# 3_-MCU.net
KiCad netlist of a schematic drawn in Altium Designer
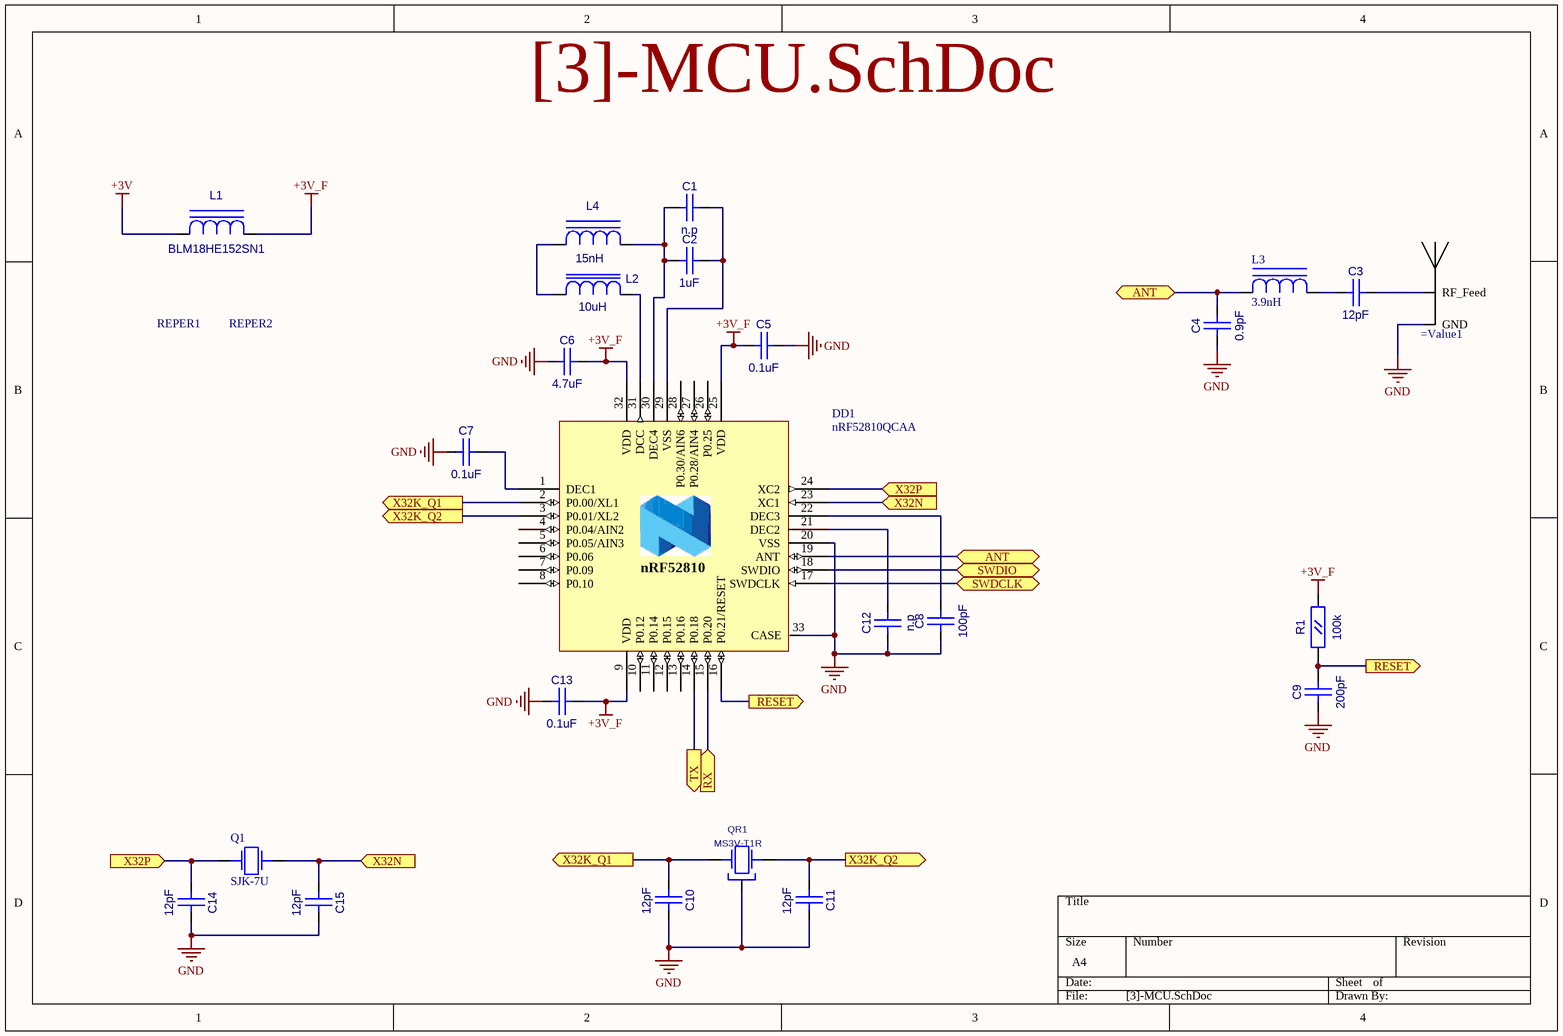
[diagram p0: [3]-MCU.SchDoc]

(export (version "E")
  (design (tool "Eeschema 10.0.6"))
  (components
    (comp (ref "=Value1")
      (value "ANTENNA_IFA_245_1MM")
      (footprint "IFA245_1mm")
      (description "Antenna 2.45GHz")
      (libsource (lib "fizik_lib") (part "ANTENNA_IFA_245_1MM"))
    )
    (comp (ref "C1")
      (value "n.p")
      (footprint "CC0805")
      (description "CC0805")
      (libsource (lib "fizik_lib") (part "CC0805"))
    )
    (comp (ref "C2")
      (value "1uF")
      (footprint "CC0603")
      (description "CC0603")
      (libsource (lib "gprs_modem_2") (part "CC0603"))
    )
    (comp (ref "C3")
      (value "12pF")
      (footprint "CC0603")
      (description "CC0603")
      (libsource (lib "") (part "CC0603_1"))
    )
    (comp (ref "C4")
      (value "0.9pF")
      (footprint "CC0603")
      (description "CC0603")
      (libsource (lib "fizik_lib") (part "CC0603"))
    )
    (comp (ref "C5")
      (value "0.1uF")
      (footprint "CC0603")
      (description "CC0603")
      (libsource (lib "gprs_modem_2") (part "CC0603"))
    )
    (comp (ref "C6")
      (value "4.7uF")
      (footprint "CC0805")
      (description "CC0805")
      (libsource (lib "fizik_lib") (part "CC0805"))
    )
    (comp (ref "C7")
      (value "0.1uF")
      (footprint "CC0603")
      (description "CC0603")
      (libsource (lib "gprs_modem_2") (part "CC0603"))
    )
    (comp (ref "C8")
      (value "100pF")
      (footprint "CC0603")
      (description "CC0603")
      (libsource (lib "gprs_modem_2") (part "CC0603"))
    )
    (comp (ref "C9")
      (value "200pF")
      (footprint "CC0603")
      (description "CC0603")
      (libsource (lib "gprs_modem_2") (part "CC0603"))
    )
    (comp (ref "C10")
      (value "12pF")
      (footprint "CC0603")
      (description "CC0603")
      (libsource (lib "gprs_modem_2") (part "CC0603"))
    )
    (comp (ref "C11")
      (value "12pF")
      (footprint "CC0603")
      (description "CC0603")
      (libsource (lib "gprs_modem_2") (part "CC0603"))
    )
    (comp (ref "C12")
      (value "n.p")
      (footprint "CC0603")
      (description "CC0603")
      (libsource (lib "gprs_modem_2") (part "CC0603"))
    )
    (comp (ref "C13")
      (value "0.1uF")
      (footprint "CC0603")
      (description "CC0603")
      (libsource (lib "gprs_modem_2") (part "CC0603"))
    )
    (comp (ref "C14")
      (value "12pF")
      (footprint "CC0603")
      (description "CC0603")
      (libsource (lib "gprs_modem_2") (part "CC0603"))
    )
    (comp (ref "C15")
      (value "12pF")
      (footprint "CC0603")
      (description "CC0603")
      (libsource (lib "gprs_modem_2") (part "CC0603"))
    )
    (comp (ref "DD1")
      (value "nRF52810QCAA")
      (footprint "QFN-32")
      (description "BLE 5 controller")
      (libsource (lib "fizik_lib") (part "NRF52810QCAA"))
    )
    (comp (ref "L1")
      (value "BLM18HE152SN1")
      (footprint "L0603")
      (description "L0603")
      (libsource (lib "gprs_modem_2") (part "L0603"))
    )
    (comp (ref "L2")
      (value "10uH")
      (footprint "RC0805")
      (description "L0805")
      (libsource (lib "gprs_modem_2") (part "L0805"))
    )
    (comp (ref "L3")
      (value "3.9nH")
      (footprint "L0402")
      (description "L0402")
      (libsource (lib "gprs_modem_2") (part "L0402"))
    )
    (comp (ref "L4")
      (value "15nH")
      (footprint "L0603")
      (description "L0603")
      (libsource (lib "fizik_lib") (part "L0603"))
    )
    (comp (ref "Q1")
      (value "SJK-7U")
      (footprint "QUARTZ_3225_4")
      (description "3.2x2.5mm 4 pin SMD quartz crystal")
      (libsource (lib "fizik_lib") (part "SJK-7U"))
    )
    (comp (ref "QR1")
      (value "MS3V-T1R")
      (footprint "MS3V-T1R")
      (description "CRYSTAL_32768 Hz")
      (libsource (lib "gprs_modem_2") (part "MS3V-T1R"))
    )
    (comp (ref "R1")
      (value "100k")
      (footprint "RC0603")
      (description "RC0603")
      (libsource (lib "gprs_modem_2") (part "RC0603"))
    )
    (comp (ref "REPER1")
      (value "REPER1.2")
      (footprint "REPER1.2")
      (libsource (lib "gprs_modem_2") (part "REPER1.2"))
    )
    (comp (ref "REPER2")
      (value "REPER1.2")
      (footprint "REPER1.2")
      (libsource (lib "gprs_modem_2") (part "REPER1.2"))
    )
  )
  (nets
    (net (code "1") (name "+3V") (class "Default")
      (node (ref "L1") (pin "1") (pinfunction "A_1") (pintype "passive"))
    )
    (net (code "2") (name "+3V_F") (class "Default")
      (node (ref "C13") (pin "2") (pinfunction "B_2") (pintype "passive"))
      (node (ref "C5") (pin "1") (pinfunction "A_1") (pintype "passive"))
      (node (ref "C6") (pin "2") (pinfunction "B_2") (pintype "passive"))
      (node (ref "DD1") (pin "25") (pinfunction "VDD_25") (pintype "power_in"))
      (node (ref "DD1") (pin "32") (pinfunction "VDD_32") (pintype "power_in"))
      (node (ref "DD1") (pin "9") (pinfunction "VDD_9") (pintype "power_in"))
      (node (ref "L1") (pin "2") (pinfunction "C_2") (pintype "passive"))
      (node (ref "R1") (pin "2") (pinfunction "B_2") (pintype "passive"))
    )
    (net (code "3") (name "/ANT") (class "Default")
      (node (ref "C4") (pin "2") (pinfunction "B_2") (pintype "passive"))
      (node (ref "DD1") (pin "19") (pinfunction "ANT_19") (pintype "bidirectional"))
      (node (ref "L3") (pin "1") (pinfunction "A_1") (pintype "passive"))
    )
    (net (code "4") (name "/RESET") (class "Default")
      (node (ref "C9") (pin "2") (pinfunction "B_2") (pintype "passive"))
      (node (ref "DD1") (pin "16") (pinfunction "P0.21/RESET_16") (pintype "bidirectional"))
      (node (ref "R1") (pin "1") (pinfunction "A_1") (pintype "passive"))
    )
    (net (code "5") (name "/RX") (class "Default")
      (node (ref "DD1") (pin "15") (pinfunction "P0.20_15") (pintype "bidirectional"))
    )
    (net (code "6") (name "/SWDCLK") (class "Default")
      (node (ref "DD1") (pin "17") (pinfunction "SWDCLK_17") (pintype "input"))
    )
    (net (code "7") (name "/SWDIO") (class "Default")
      (node (ref "DD1") (pin "18") (pinfunction "SWDIO_18") (pintype "bidirectional"))
    )
    (net (code "8") (name "/TX") (class "Default")
      (node (ref "DD1") (pin "14") (pinfunction "P0.18_14") (pintype "bidirectional"))
    )
    (net (code "9") (name "/X32K_Q1") (class "Default")
      (node (ref "C10") (pin "1") (pinfunction "A_1") (pintype "passive"))
      (node (ref "DD1") (pin "2") (pinfunction "P0.00/XL1_2") (pintype "bidirectional"))
      (node (ref "QR1") (pin "2") (pinfunction "X2_2") (pintype "passive"))
    )
    (net (code "10") (name "/X32K_Q2") (class "Default")
      (node (ref "C11") (pin "1") (pinfunction "A_1") (pintype "passive"))
      (node (ref "DD1") (pin "3") (pinfunction "P0.01/XL2_3") (pintype "bidirectional"))
      (node (ref "QR1") (pin "1") (pinfunction "X1_1") (pintype "passive"))
    )
    (net (code "11") (name "/X32N") (class "Default")
      (node (ref "C15") (pin "1") (pinfunction "A_1") (pintype "passive"))
      (node (ref "DD1") (pin "23") (pinfunction "XC1_23") (pintype "input"))
      (node (ref "Q1") (pin "3") (pintype "passive"))
    )
    (net (code "12") (name "/X32P") (class "Default")
      (node (ref "C14") (pin "1") (pinfunction "A_1") (pintype "passive"))
      (node (ref "DD1") (pin "24") (pinfunction "XC2_24") (pintype "output"))
      (node (ref "Q1") (pin "1") (pintype "passive"))
    )
    (net (code "13") (name "GND") (class "Default")
      (node (ref "=Value1") (pin "2") (pinfunction "GND_2") (pintype "passive"))
      (node (ref "C10") (pin "2") (pinfunction "B_2") (pintype "passive"))
      (node (ref "C11") (pin "2") (pinfunction "B_2") (pintype "passive"))
      (node (ref "C12") (pin "1") (pinfunction "A_1") (pintype "passive"))
      (node (ref "C13") (pin "1") (pinfunction "A_1") (pintype "passive"))
      (node (ref "C14") (pin "2") (pinfunction "B_2") (pintype "passive"))
      (node (ref "C15") (pin "2") (pinfunction "B_2") (pintype "passive"))
      (node (ref "C4") (pin "1") (pinfunction "A_1") (pintype "passive"))
      (node (ref "C5") (pin "2") (pinfunction "B_2") (pintype "passive"))
      (node (ref "C6") (pin "1") (pinfunction "A_1") (pintype "passive"))
      (node (ref "C7") (pin "1") (pinfunction "A_1") (pintype "passive"))
      (node (ref "C8") (pin "1") (pinfunction "A_1") (pintype "passive"))
      (node (ref "C9") (pin "1") (pinfunction "A_1") (pintype "passive"))
      (node (ref "DD1") (pin "20") (pinfunction "VSS_20") (pintype "power_in"))
      (node (ref "DD1") (pin "33") (pinfunction "CASE_33") (pintype "passive"))
      (node (ref "QR1") (pin "3") (pinfunction "3_3") (pintype "passive"))
    )
    (net (code "14") (name "Net-(=Value1-RF_Feed)") (class "Default")
      (node (ref "=Value1") (pin "1") (pinfunction "RF_Feed_1") (pintype "passive"))
      (node (ref "C3") (pin "2") (pinfunction "B_2") (pintype "passive"))
    )
    (net (code "15") (name "Net-(C1-A)") (class "Default")
      (node (ref "C1") (pin "1") (pinfunction "A_1") (pintype "passive"))
      (node (ref "C2") (pin "1") (pinfunction "A_1") (pintype "passive"))
      (node (ref "DD1") (pin "30") (pinfunction "DEC4_30") (pintype "power_in"))
      (node (ref "L4") (pin "2") (pinfunction "C_2") (pintype "passive"))
    )
    (net (code "16") (name "Net-(C1-B)") (class "Default")
      (node (ref "C1") (pin "2") (pinfunction "B_2") (pintype "passive"))
      (node (ref "C2") (pin "2") (pinfunction "B_2") (pintype "passive"))
      (node (ref "DD1") (pin "29") (pinfunction "VSS_29") (pintype "power_in"))
    )
    (net (code "17") (name "Net-(C3-A)") (class "Default")
      (node (ref "C3") (pin "1") (pinfunction "A_1") (pintype "passive"))
      (node (ref "L3") (pin "2") (pinfunction "C_2") (pintype "passive"))
    )
    (net (code "18") (name "Net-(C7-B)") (class "Default")
      (node (ref "C7") (pin "2") (pinfunction "B_2") (pintype "passive"))
      (node (ref "DD1") (pin "1") (pinfunction "DEC1_1") (pintype "power_in"))
    )
    (net (code "19") (name "Net-(C8-B)") (class "Default")
      (node (ref "C8") (pin "2") (pinfunction "B_2") (pintype "passive"))
      (node (ref "DD1") (pin "22") (pinfunction "DEC3_22") (pintype "power_in"))
    )
    (net (code "20") (name "Net-(C12-B)") (class "Default")
      (node (ref "C12") (pin "2") (pinfunction "B_2") (pintype "passive"))
      (node (ref "DD1") (pin "21") (pinfunction "DEC2_21") (pintype "power_in"))
    )
    (net (code "21") (name "Net-(DD1-DCC)") (class "Default")
      (node (ref "DD1") (pin "31") (pinfunction "DCC_31") (pintype "output"))
      (node (ref "L2") (pin "2") (pinfunction "B_2") (pintype "passive"))
    )
    (net (code "22") (name "Net-(L2-A)") (class "Default")
      (node (ref "L2") (pin "1") (pinfunction "A_1") (pintype "passive"))
      (node (ref "L4") (pin "1") (pinfunction "A_1") (pintype "passive"))
    )
    (net (code "23") (name "unconnected-(DD1-P0.04{slash}AIN2-Pad4)") (class "Default")
      (node (ref "DD1") (pin "4") (pinfunction "P0.04/AIN2_4") (pintype "bidirectional"))
    )
    (net (code "24") (name "unconnected-(DD1-P0.05{slash}AIN3-Pad5)") (class "Default")
      (node (ref "DD1") (pin "5") (pinfunction "P0.05/AIN3_5") (pintype "bidirectional"))
    )
    (net (code "25") (name "unconnected-(DD1-P0.06-Pad6)") (class "Default")
      (node (ref "DD1") (pin "6") (pinfunction "P0.06_6") (pintype "bidirectional"))
    )
    (net (code "26") (name "unconnected-(DD1-P0.09-Pad7)") (class "Default")
      (node (ref "DD1") (pin "7") (pinfunction "P0.09_7") (pintype "bidirectional"))
    )
    (net (code "27") (name "unconnected-(DD1-P0.10-Pad8)") (class "Default")
      (node (ref "DD1") (pin "8") (pinfunction "P0.10_8") (pintype "bidirectional"))
    )
    (net (code "28") (name "unconnected-(DD1-P0.12-Pad10)") (class "Default")
      (node (ref "DD1") (pin "10") (pinfunction "P0.12_10") (pintype "bidirectional"))
    )
    (net (code "29") (name "unconnected-(DD1-P0.14-Pad11)") (class "Default")
      (node (ref "DD1") (pin "11") (pinfunction "P0.14_11") (pintype "bidirectional"))
    )
    (net (code "30") (name "unconnected-(DD1-P0.15-Pad12)") (class "Default")
      (node (ref "DD1") (pin "12") (pinfunction "P0.15_12") (pintype "bidirectional"))
    )
    (net (code "31") (name "unconnected-(DD1-P0.16-Pad13)") (class "Default")
      (node (ref "DD1") (pin "13") (pinfunction "P0.16_13") (pintype "bidirectional"))
    )
    (net (code "32") (name "unconnected-(DD1-P0.25-Pad26)") (class "Default")
      (node (ref "DD1") (pin "26") (pinfunction "P0.25_26") (pintype "bidirectional"))
    )
    (net (code "33") (name "unconnected-(DD1-P0.28{slash}AIN4-Pad27)") (class "Default")
      (node (ref "DD1") (pin "27") (pinfunction "P0.28/AIN4_27") (pintype "bidirectional"))
    )
    (net (code "34") (name "unconnected-(DD1-P0.30{slash}AIN6-Pad28)") (class "Default")
      (node (ref "DD1") (pin "28") (pinfunction "P0.30/AIN6_28") (pintype "bidirectional"))
    )
    (net (code "35") (name "unconnected-(REPER1-Pad1)") (class "Default")
      (node (ref "REPER1") (pin "1") (pintype "passive"))
    )
    (net (code "36") (name "unconnected-(REPER2-Pad1)") (class "Default")
      (node (ref "REPER2") (pin "1") (pintype "passive"))
    )
  )
)
